# Battery_Charger.net
KiCad netlist of a schematic drawn in Altium Designer
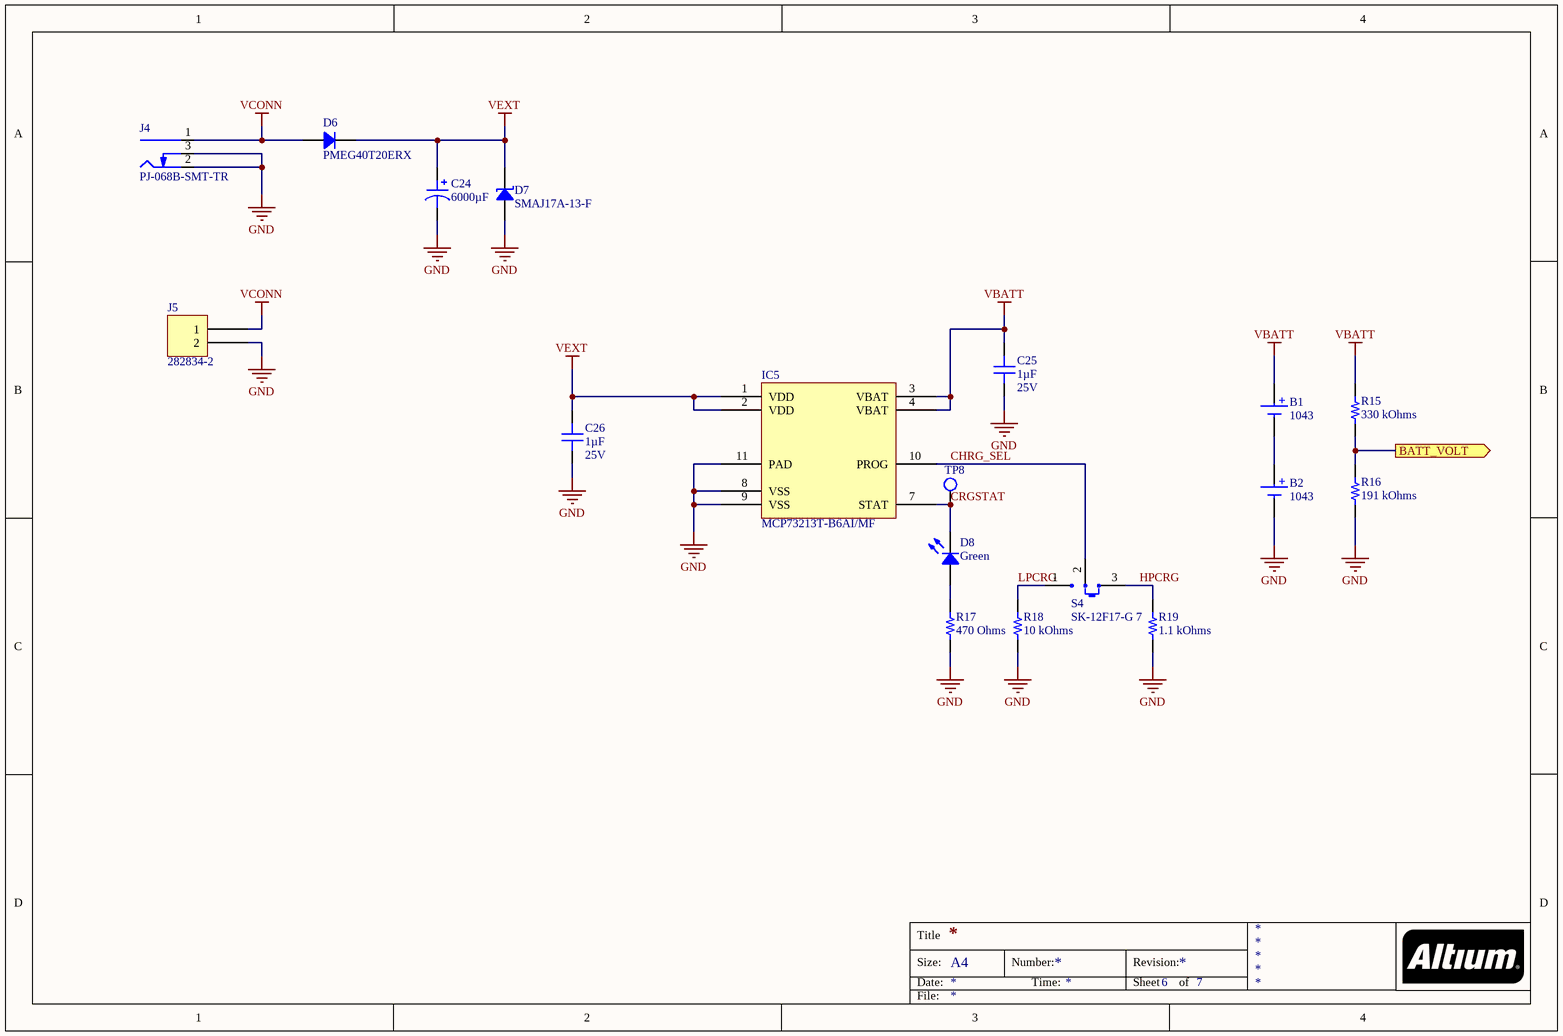
[diagram p0: Battery Charger.SchDoc]

(export (version "E")
  (design (tool "Eeschema 10.0.6"))
  (components
    (comp (ref "B1")
      (value "1043")
      (footprint "KEYSTONE 1043")
      (description "BATTERY HOLDER 18650 PC PIN")
      (fields (field (name "MANUFACTURER") "Keystone Electronics"))
      (libsource (lib "altiumlibrary.com") (part "Keystone 1043"))
    )
    (comp (ref "B2")
      (value "1043")
      (footprint "KEYSTONE 1043")
      (description "BATTERY HOLDER 18650 PC PIN")
      (fields (field (name "MANUFACTURER") "Keystone Electronics"))
      (libsource (lib "altiumlibrary.com") (part "Keystone 1043"))
    )
    (comp (ref "C24")
      (value "6000µF")
      (footprint "CAP TH ALUM ELEC D18.00mm S7.50mm H33.00mm")
      (description "CAP ALUM 6000UF 35V T/H")
      (fields
        (field (name "PART NUMBER") "ELBK350ELL602AMN3S")
        (field (name "MANUFACTURER") "United Chemi-Con")
      )
      (libsource (lib "altiumlibrary.com") (part "Polarised Capacitor"))
    )
    (comp (ref "C25")
      (value "1µF")
      (footprint "CAP 0603_1608")
      (description "CAP CER 1UF 25V X5R 0603")
      (fields
        (field (name "PART NUMBER") "CL10A105KA8NNNC")
        (field (name "MANUFACTURER") "Samsung Electro-Mechanics")
        (field (name "VOLTAGE - RATED") "25V")
      )
      (libsource (lib "altiumlibrary.com") (part "Capacitor"))
    )
    (comp (ref "C26")
      (value "1µF")
      (footprint "CAP 0603_1608")
      (description "CAP CER 1UF 25V X5R 0603")
      (fields
        (field (name "PART NUMBER") "CL10A105KA8NNNC")
        (field (name "MANUFACTURER") "Samsung Electro-Mechanics")
        (field (name "VOLTAGE - RATED") "25V")
      )
      (libsource (lib "altiumlibrary.com") (part "Capacitor"))
    )
    (comp (ref "D6")
      (value "PMEG40T20ERX")
      (footprint "SOD-123W")
      (description "DIODE SCHOTTKY 40V 2A SOD123W")
      (fields (field (name "MANUFACTURER") "Nexperia USA Inc."))
      (libsource (lib "altiumlibrary.com") (part "Diode"))
    )
    (comp (ref "D7")
      (value "SMAJ17A-13-F")
      (footprint "DO214AC SMA")
      (description "TVS DIODE 17V 27.6V SMA")
      (fields (field (name "MANUFACTURER") "Diodes Incorporated"))
      (libsource (lib "altiumlibrary.com") (part "DIODE TVS UNI"))
    )
    (comp (ref "D8")
      (value "Green")
      (footprint "LED 1206_3216 GREEN")
      (description "LED GREEN CLEAR 1206 SMD")
      (fields
        (field (name "PART NUMBER") "QTLP650C4TR")
        (field (name "MANUFACTURER") "Everlight Electronics Co Ltd")
      )
      (libsource (lib "altiumlibrary.com") (part "LED"))
    )
    (comp (ref "IC5")
      (value "MCP73213T-B6AI/MF")
      (footprint "MICROCHIP DFN-10 3MMX3MM MF")
      (description "DUAL CELL OVP BATTERY CHARGER")
      (fields (field (name "MANUFACTURER") "Microchip Technology"))
      (libsource (lib "altiumlibrary.com") (part "Microchip MCP73213x"))
    )
    (comp (ref "J4")
      (value "PJ-068B-SMT-TR")
      (footprint "CUI PJ-068B-SMT")
      (description "CONN PWR JACK 2.5X5.5MM SOLDER")
      (fields (field (name "MANUFACTURER") "CUI Devices"))
      (libsource (lib "altiumlibrary.com") (part "Barrel Connector"))
    )
    (comp (ref "J5")
      (value "282834-2")
      (footprint "TE 282834-2")
      (description "TERM BLK 2P SIDE ENT 2.54MM PCB")
      (fields (field (name "MANUFACTURER") "TE Connectivity AMP Connectors") (field (name "VOLTAGE") "150V"))
      (libsource (lib "altiumlibrary.com") (part "2 Pin"))
    )
    (comp (ref "R15")
      (value "330 kOhms")
      (footprint "RES 0603_1608")
      (description "RES SMD 330K OHM 5% 1/4W 0603")
      (fields
        (field (name "PART NUMBER") "ERJ-PA3J334V")
        (field (name "MANUFACTURER") "Panasonic Electronic Components")
      )
      (libsource (lib "altiumlibrary.com") (part "Resistor"))
    )
    (comp (ref "R16")
      (value "191 kOhms")
      (footprint "RES 0603_1608")
      (description "RES SMD 191K OHM 1% 1/10W 0603")
      (fields
        (field (name "PART NUMBER") "ERJ-3EKF1913V")
        (field (name "MANUFACTURER") "Panasonic Electronic Components")
      )
      (libsource (lib "altiumlibrary.com") (part "Resistor"))
    )
    (comp (ref "R17")
      (value "470 Ohms")
      (footprint "RES 0603_1608")
      (description "CRGCQ 0603 470R 5%")
      (fields
        (field (name "PART NUMBER") "CRGCQ0603J470R")
        (field (name "MANUFACTURER") "TE Connectivity Passive Product")
      )
      (libsource (lib "altiumlibrary.com") (part "Resistor"))
    )
    (comp (ref "R18")
      (value "10 kOhms")
      (footprint "RES 0603_1608")
      (description "RES SMD 10K OHM 5% 1/4W 0603")
      (fields
        (field (name "PART NUMBER") "ERJ-PA3J103V")
        (field (name "MANUFACTURER") "Panasonic Electronic Components")
      )
      (libsource (lib "altiumlibrary.com") (part "Resistor"))
    )
    (comp (ref "R19")
      (value "1.1 kOhms")
      (footprint "RES 0603_1608")
      (description "RES SMD 1.1K OHM 1% 1/10W 0603")
      (fields
        (field (name "PART NUMBER") "ERJ-3EKF1101V")
        (field (name "MANUFACTURER") "Panasonic Electronic Components")
      )
      (libsource (lib "altiumlibrary.com") (part "Resistor"))
    )
    (comp (ref "S4")
      (value "SK-12F17-G 7")
      (footprint "C&K SK-12F17-G 7")
      (description "SWITCH SLIDE SPDT 300MA 30V")
      (fields (field (name "MANUFACTURER") "C&K"))
      (libsource (lib "altiumlibrary.com") (part "C&K SK-12F17-G 7"))
    )
    (comp (ref "TP8")
      (value "Test Point")
      (footprint "TestPoint-1.5mm")
      (libsource (lib "CelestialUseful") (part "Test Point"))
    )
  )
  (nets
    (net (code "1") (name "/BATT_VOLT") (class "Default")
      (node (ref "R15") (pin "1") (pinfunction "1_1") (pintype "passive"))
      (node (ref "R16") (pin "2") (pinfunction "2_2") (pintype "passive"))
    )
    (net (code "2") (name "/CHRG_SEL") (class "Default")
      (node (ref "IC5") (pin "10") (pinfunction "PROG_10") (pintype "passive"))
      (node (ref "S4") (pin "2") (pinfunction "COM_2") (pintype "passive"))
    )
    (net (code "3") (name "/CRGSTAT") (class "Default")
      (node (ref "D8") (pin "2") (pinfunction "2_2") (pintype "passive"))
      (node (ref "IC5") (pin "7") (pinfunction "STAT_7") (pintype "passive"))
      (node (ref "TP8") (pin "1") (pinfunction "TP_1") (pintype "passive"))
    )
    (net (code "4") (name "/HPCRG") (class "Default")
      (node (ref "R19") (pin "2") (pinfunction "2_2") (pintype "passive"))
      (node (ref "S4") (pin "3") (pinfunction "3_3") (pintype "passive"))
    )
    (net (code "5") (name "/LPCRG") (class "Default")
      (node (ref "R18") (pin "2") (pinfunction "2_2") (pintype "passive"))
      (node (ref "S4") (pin "1") (pinfunction "1_1") (pintype "passive"))
    )
    (net (code "6") (name "GND") (class "Default")
      (node (ref "B2") (pin "2") (pinfunction "-_2") (pintype "passive"))
      (node (ref "C24") (pin "2") (pinfunction "2_2") (pintype "passive"))
      (node (ref "C25") (pin "2") (pinfunction "2_2") (pintype "passive"))
      (node (ref "C26") (pin "2") (pinfunction "2_2") (pintype "passive"))
      (node (ref "D7") (pin "1") (pinfunction "1_1") (pintype "passive"))
      (node (ref "IC5") (pin "11") (pinfunction "PAD_11") (pintype "passive"))
      (node (ref "IC5") (pin "8") (pinfunction "VSS_8") (pintype "passive"))
      (node (ref "IC5") (pin "9") (pinfunction "VSS_9") (pintype "passive"))
      (node (ref "J4") (pin "2") (pinfunction "Outer_2") (pintype "passive"))
      (node (ref "J4") (pin "3") (pinfunction "SW_3") (pintype "passive"))
      (node (ref "J5") (pin "2") (pinfunction "2_2") (pintype "passive"))
      (node (ref "R16") (pin "1") (pinfunction "1_1") (pintype "passive"))
      (node (ref "R17") (pin "1") (pinfunction "1_1") (pintype "passive"))
      (node (ref "R18") (pin "1") (pinfunction "1_1") (pintype "passive"))
      (node (ref "R19") (pin "1") (pinfunction "1_1") (pintype "passive"))
    )
    (net (code "7") (name "Net-(B1--)") (class "Default")
      (node (ref "B1") (pin "2") (pinfunction "-_2") (pintype "passive"))
      (node (ref "B2") (pin "1") (pinfunction "+_1") (pintype "passive"))
    )
    (net (code "8") (name "Net-(D8-Pad1)") (class "Default")
      (node (ref "D8") (pin "1") (pinfunction "1_1") (pintype "passive"))
      (node (ref "R17") (pin "2") (pinfunction "2_2") (pintype "passive"))
    )
    (net (code "9") (name "VBATT") (class "Default")
      (node (ref "B1") (pin "1") (pinfunction "+_1") (pintype "passive"))
      (node (ref "C25") (pin "1") (pinfunction "1_1") (pintype "passive"))
      (node (ref "IC5") (pin "3") (pinfunction "VBAT_3") (pintype "passive"))
      (node (ref "IC5") (pin "4") (pinfunction "VBAT_4") (pintype "passive"))
      (node (ref "R15") (pin "2") (pinfunction "2_2") (pintype "passive"))
    )
    (net (code "10") (name "VCONN") (class "Default")
      (node (ref "D6") (pin "1") (pinfunction "1_1") (pintype "passive"))
      (node (ref "J4") (pin "1") (pinfunction "Centre_1") (pintype "passive"))
      (node (ref "J5") (pin "1") (pinfunction "1_1") (pintype "passive"))
    )
    (net (code "11") (name "VEXT") (class "Default")
      (node (ref "C24") (pin "1") (pinfunction "1_1") (pintype "passive"))
      (node (ref "C26") (pin "1") (pinfunction "1_1") (pintype "passive"))
      (node (ref "D6") (pin "2") (pinfunction "2_2") (pintype "passive"))
      (node (ref "D7") (pin "2") (pinfunction "2_2") (pintype "passive"))
      (node (ref "IC5") (pin "1") (pinfunction "VDD_1") (pintype "passive"))
      (node (ref "IC5") (pin "2") (pinfunction "VDD_2") (pintype "passive"))
    )
  )
)
